# v0_3_0.net
KiCad netlist of a schematic drawn in EAGLE
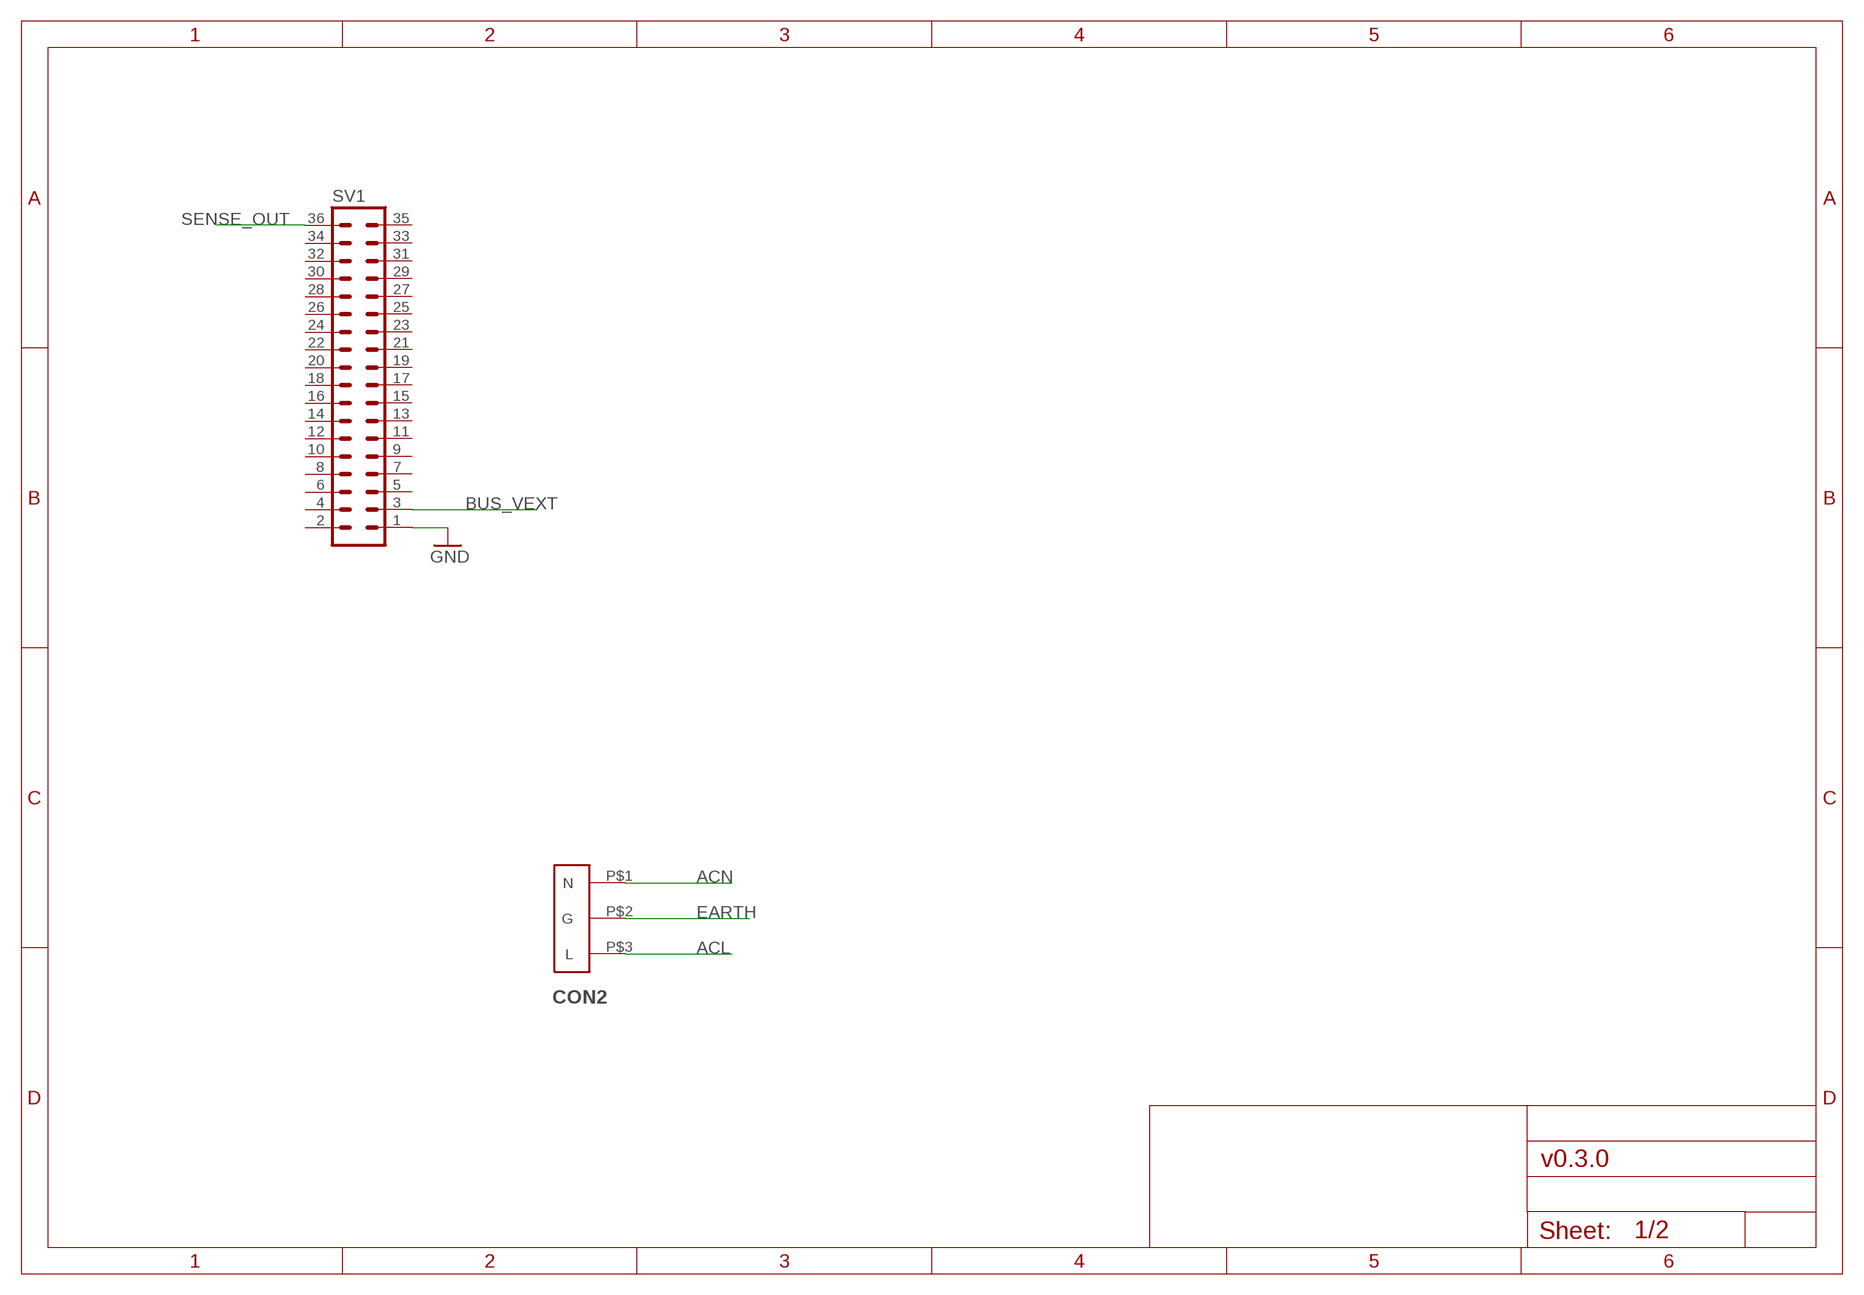
[diagram p0: schematic, sheet 1]
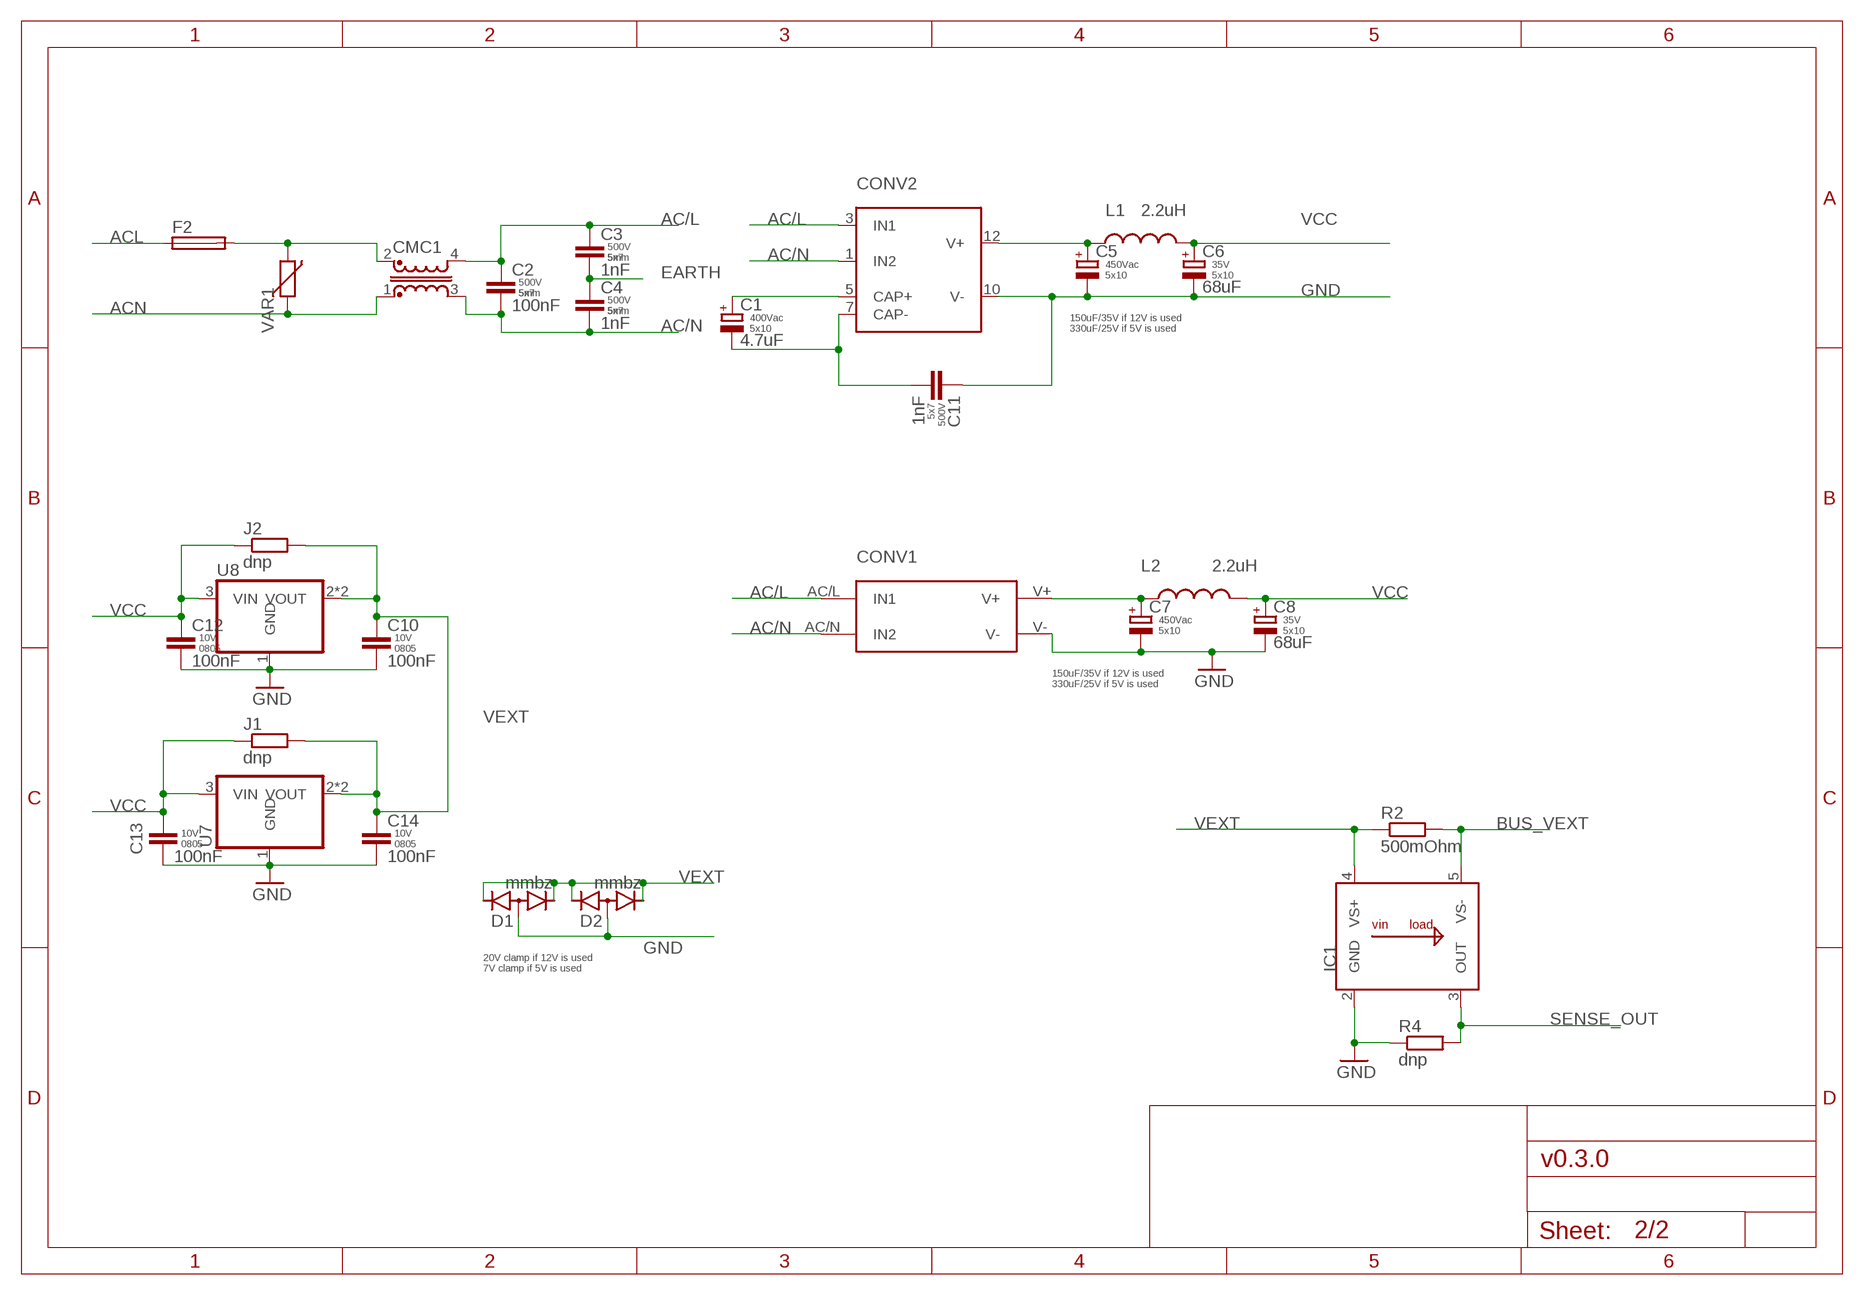
[diagram p1: schematic, sheet 2]

(export (version "E")
  (design (tool "Eeschema 10.0.6"))
  (components
    (comp (ref "CON2")
      (value "4300.0101")
      (footprint "eagle-import:IEC-C6")
      (libsource (lib "eagle-import") (part "4300.0101"))
    )
    (comp (ref "SV1")
      (value "MA18-2")
      (footprint "eagle-import:MA18-2")
      (libsource (lib "eagle-import") (part "MA18-2"))
    )
    (comp (ref "C1")
      (value "4.7uF")
      (footprint "eagle-import:CAPPRD508W65D1000H1600B")
      (fields
        (field (name "PACKAGE") "5x10")
        (field (name "RATING") "450Vac")
        (field (name "RATING_1") "400Vac")
      )
      (libsource (lib "eagle-import") (part "CAP-POL-5PX10WX16H"))
    )
    (comp (ref "C2")
      (value "100nF")
      (footprint "eagle-import:C050-025X075")
      (fields
        (field (name "RATING") "500V")
        (field (name "DIMENSIONS") "5mm")
        (field (name "RATING_1") "500V")
      )
      (libsource (lib "eagle-import") (part "CAP-P5W6H8T2.5"))
    )
    (comp (ref "C3")
      (value "1nF")
      (footprint "eagle-import:C050-025X075")
      (fields
        (field (name "RATING") "500V")
        (field (name "DIMENSIONS") "5mm")
        (field (name "RATING_1") "500V")
      )
      (libsource (lib "eagle-import") (part "CAP-P5W6H8T2.5"))
    )
    (comp (ref "C4")
      (value "1nF")
      (footprint "eagle-import:C050-025X075")
      (fields
        (field (name "RATING") "500V")
        (field (name "DIMENSIONS") "5mm")
        (field (name "RATING_1") "500V")
      )
      (libsource (lib "eagle-import") (part "CAP-P5W6H8T2.5"))
    )
    (comp (ref "C5")
      (value "CAP-POL-5PX10WX16H")
      (footprint "eagle-import:CAPPRD508W65D1000H1600B")
      (libsource (lib "eagle-import") (part "CAP-POL-5PX10WX16H"))
    )
    (comp (ref "C6")
      (value "68uF")
      (footprint "eagle-import:CAPPRD508W65D1000H1600B")
      (fields
        (field (name "PACKAGE") "5x10")
        (field (name "RATING") "450Vac")
        (field (name "RATING_1") "35V")
      )
      (libsource (lib "eagle-import") (part "CAP-POL-5PX10WX16H"))
    )
    (comp (ref "C7")
      (value "CAP-POL-5PX10WX16H")
      (footprint "eagle-import:CAPPRD508W65D1000H1600B")
      (libsource (lib "eagle-import") (part "CAP-POL-5PX10WX16H"))
    )
    (comp (ref "C8")
      (value "68uF")
      (footprint "eagle-import:CAPPRD508W65D1000H1600B")
      (fields
        (field (name "PACKAGE") "5x10")
        (field (name "RATING") "450Vac")
        (field (name "RATING_1") "35V")
      )
      (libsource (lib "eagle-import") (part "CAP-POL-5PX10WX16H"))
    )
    (comp (ref "C10")
      (value "100nF")
      (footprint "eagle-import:C0805")
      (fields (field (name "RATING") "10V") (field (name "PACKAGE") "0805"))
      (libsource (lib "eagle-import") (part "CAP-0805"))
    )
    (comp (ref "C11")
      (value "1nF")
      (footprint "eagle-import:C050-025X075")
      (fields (field (name "RATING") "500V") (field (name "PACKAGE") "5x7"))
      (libsource (lib "eagle-import") (part "CAP-P5W6H8T2.5"))
    )
    (comp (ref "C12")
      (value "100nF")
      (footprint "eagle-import:C0805")
      (libsource (lib "eagle-import") (part "CAP-0805"))
    )
    (comp (ref "C13")
      (value "100nF")
      (footprint "eagle-import:C0805")
      (libsource (lib "eagle-import") (part "CAP-0805"))
    )
    (comp (ref "C14")
      (value "100nF")
      (footprint "eagle-import:C0805")
      (fields (field (name "RATING") "10V") (field (name "PACKAGE") "0805"))
      (libsource (lib "eagle-import") (part "CAP-0805"))
    )
    (comp (ref "CMC1")
      (value "DLD-302U-1A")
      (footprint "eagle-import:DLD")
      (libsource (lib "eagle-import") (part "DLD-302U-1A"))
    )
    (comp (ref "CONV1")
      (value "IRM-03-12V")
      (footprint "eagle-import:IRM-03")
      (libsource (lib "eagle-import") (part "IRM-03-12V"))
    )
    (comp (ref "CONV2")
      (value "AMEOF312SJZ")
      (footprint "eagle-import:AMEOF3-JZ")
      (libsource (lib "eagle-import") (part "AMEOF312SJZ"))
    )
    (comp (ref "D1")
      (value "mmbz")
      (footprint "eagle-import:SOT23")
      (libsource (lib "eagle-import") (part "DIODE-2CA|ACSOT23"))
    )
    (comp (ref "D2")
      (value "mmbz")
      (footprint "eagle-import:SOT23")
      (libsource (lib "eagle-import") (part "DIODE-2CA|ACSOT23"))
    )
    (comp (ref "F2")
      (value "ZH8")
      (footprint "eagle-import:ZH8X2")
      (libsource (lib "eagle-import") (part "ZH8"))
    )
    (comp (ref "IC1")
      (value "ZXCT1021")
      (footprint "eagle-import:SOT95P240X110-5")
      (libsource (lib "eagle-import") (part "ZXCT1021"))
    )
    (comp (ref "J1")
      (value "dnp")
      (footprint "eagle-import:R0805")
      (libsource (lib "eagle-import") (part "R-EU_R0805"))
    )
    (comp (ref "J2")
      (value "dnp")
      (footprint "eagle-import:R0805")
      (libsource (lib "eagle-import") (part "R-EU_R0805"))
    )
    (comp (ref "L1")
      (value "2.2uH")
      (footprint "eagle-import:COIL0608")
      (libsource (lib "eagle-import") (part "COIL0608-0.022"))
    )
    (comp (ref "L2")
      (value "2.2uH")
      (footprint "eagle-import:COIL0608")
      (libsource (lib "eagle-import") (part "COIL0608-0.022"))
    )
    (comp (ref "R2")
      (value "500mOhm")
      (footprint "eagle-import:R0805")
      (libsource (lib "eagle-import") (part "R-EU_R0805"))
    )
    (comp (ref "R4")
      (value "dnp")
      (footprint "eagle-import:R0603")
      (libsource (lib "eagle-import") (part "R-EU_R0603"))
    )
    (comp (ref "U7")
      (value "LD1117S50")
      (footprint "eagle-import:SOT230P700X180-4")
      (libsource (lib "eagle-import") (part "LD1117S50"))
    )
    (comp (ref "U8")
      (value "LD1117S50")
      (footprint "eagle-import:SOT230P700X180-4")
      (libsource (lib "eagle-import") (part "LD1117S50"))
    )
    (comp (ref "VAR1")
      (value "S14K250")
      (footprint "eagle-import:C7.5B4")
      (libsource (lib "eagle-import") (part "S14K250"))
    )
  )
  (nets
    (net (code "1") (name "ACL") (class "Default")
      (node (ref "CON2") (pin "P$3") (pinfunction "L_P$3") (pintype "bidirectional"))
      (node (ref "F2") (pin "1") (pinfunction "1_1") (pintype "passive"))
      (node (ref "F2") (pin "1A") (pinfunction "1_1A") (pintype "passive"))
    )
    (net (code "2") (name "ACN") (class "Default")
      (node (ref "CMC1") (pin "1") (pinfunction "1_1") (pintype "passive"))
      (node (ref "CON2") (pin "P$1") (pinfunction "N_P$1") (pintype "bidirectional"))
      (node (ref "VAR1") (pin "1") (pinfunction "1_1") (pintype "passive"))
    )
    (net (code "3") (name "AC{slash}L") (class "Default")
      (node (ref "C2") (pin "1") (pinfunction "1_1") (pintype "passive"))
      (node (ref "C3") (pin "1") (pinfunction "1_1") (pintype "passive"))
      (node (ref "CMC1") (pin "4") (pinfunction "4_4") (pintype "passive"))
      (node (ref "CONV1") (pin "AC/L") (pinfunction "IN1_AC/L") (pintype "bidirectional"))
      (node (ref "CONV2") (pin "3") (pinfunction "IN1_3") (pintype "bidirectional"))
    )
    (net (code "4") (name "AC{slash}N") (class "Default")
      (node (ref "C2") (pin "2") (pinfunction "2_2") (pintype "passive"))
      (node (ref "C4") (pin "2") (pinfunction "2_2") (pintype "passive"))
      (node (ref "CMC1") (pin "3") (pinfunction "3_3") (pintype "passive"))
      (node (ref "CONV1") (pin "AC/N") (pinfunction "IN2_AC/N") (pintype "bidirectional"))
      (node (ref "CONV2") (pin "1") (pinfunction "IN2_1") (pintype "bidirectional"))
    )
    (net (code "5") (name "BUS_VEXT") (class "Default")
      (node (ref "IC1") (pin "5") (pinfunction "VS-_5") (pintype "bidirectional"))
      (node (ref "R2") (pin "2") (pinfunction "2_2") (pintype "passive"))
      (node (ref "SV1") (pin "3") (pinfunction "3_3") (pintype "passive"))
    )
    (net (code "6") (name "EARTH") (class "Default")
      (node (ref "C3") (pin "2") (pinfunction "2_2") (pintype "passive"))
      (node (ref "C4") (pin "1") (pinfunction "1_1") (pintype "passive"))
      (node (ref "CON2") (pin "P$2") (pinfunction "G_P$2") (pintype "bidirectional"))
    )
    (net (code "7") (name "GND") (class "Default")
      (node (ref "C10") (pin "2") (pinfunction "2_2") (pintype "passive"))
      (node (ref "C11") (pin "1") (pinfunction "1_1") (pintype "passive"))
      (node (ref "C12") (pin "2") (pinfunction "2_2") (pintype "passive"))
      (node (ref "C13") (pin "2") (pinfunction "2_2") (pintype "passive"))
      (node (ref "C14") (pin "2") (pinfunction "2_2") (pintype "passive"))
      (node (ref "C5") (pin "2") (pinfunction "-_2") (pintype "passive"))
      (node (ref "C6") (pin "2") (pinfunction "-_2") (pintype "passive"))
      (node (ref "C7") (pin "2") (pinfunction "-_2") (pintype "passive"))
      (node (ref "C8") (pin "2") (pinfunction "-_2") (pintype "passive"))
      (node (ref "CONV1") (pin "V-") (pinfunction "V-_V-") (pintype "bidirectional"))
      (node (ref "CONV2") (pin "10") (pinfunction "V-_10") (pintype "bidirectional"))
      (node (ref "D1") (pin "3") (pinfunction "A_3") (pintype "passive"))
      (node (ref "D2") (pin "3") (pinfunction "A_3") (pintype "passive"))
      (node (ref "IC1") (pin "2") (pinfunction "GND_2") (pintype "bidirectional"))
      (node (ref "R4") (pin "1") (pinfunction "1_1") (pintype "passive"))
      (node (ref "SV1") (pin "1") (pinfunction "1_1") (pintype "passive"))
      (node (ref "U7") (pin "1") (pinfunction "GND_1") (pintype "power_in"))
      (node (ref "U8") (pin "1") (pinfunction "GND_1") (pintype "power_in"))
    )
    (net (code "8") (name "Net-(C1-+)") (class "Default")
      (node (ref "C1") (pin "1") (pinfunction "+_1") (pintype "passive"))
      (node (ref "CONV2") (pin "5") (pinfunction "CAP+_5") (pintype "bidirectional"))
    )
    (net (code "9") (name "Net-(C1--)") (class "Default")
      (node (ref "C1") (pin "2") (pinfunction "-_2") (pintype "passive"))
      (node (ref "C11") (pin "2") (pinfunction "2_2") (pintype "passive"))
      (node (ref "CONV2") (pin "7") (pinfunction "CAP-_7") (pintype "bidirectional"))
    )
    (net (code "10") (name "Net-(C5-+)") (class "Default")
      (node (ref "C5") (pin "1") (pinfunction "+_1") (pintype "passive"))
      (node (ref "CONV2") (pin "12") (pinfunction "V+_12") (pintype "bidirectional"))
      (node (ref "L1") (pin "P$1") (pinfunction "1_P$1") (pintype "passive"))
    )
    (net (code "11") (name "Net-(C7-+)") (class "Default")
      (node (ref "C7") (pin "1") (pinfunction "+_1") (pintype "passive"))
      (node (ref "CONV1") (pin "V+") (pinfunction "V+_V+") (pintype "bidirectional"))
      (node (ref "L2") (pin "P$1") (pinfunction "1_P$1") (pintype "passive"))
    )
    (net (code "12") (name "Net-(CMC1-Pad2)") (class "Default")
      (node (ref "CMC1") (pin "2") (pinfunction "2_2") (pintype "passive"))
      (node (ref "F2") (pin "2") (pinfunction "2_2") (pintype "passive"))
      (node (ref "F2") (pin "2A") (pinfunction "2_2A") (pintype "passive"))
      (node (ref "VAR1") (pin "2") (pinfunction "2_2") (pintype "passive"))
    )
    (net (code "13") (name "SENSE_OUT") (class "Default")
      (node (ref "IC1") (pin "3") (pinfunction "OUT_3") (pintype "bidirectional"))
      (node (ref "R4") (pin "2") (pinfunction "2_2") (pintype "passive"))
      (node (ref "SV1") (pin "36") (pinfunction "36_36") (pintype "passive"))
    )
    (net (code "14") (name "VCC") (class "Default")
      (node (ref "C12") (pin "1") (pinfunction "1_1") (pintype "passive"))
      (node (ref "C13") (pin "1") (pinfunction "1_1") (pintype "passive"))
      (node (ref "C6") (pin "1") (pinfunction "+_1") (pintype "passive"))
      (node (ref "C8") (pin "1") (pinfunction "+_1") (pintype "passive"))
      (node (ref "J1") (pin "1") (pinfunction "1_1") (pintype "passive"))
      (node (ref "J2") (pin "1") (pinfunction "1_1") (pintype "passive"))
      (node (ref "L1") (pin "P$2") (pinfunction "2_P$2") (pintype "passive"))
      (node (ref "L2") (pin "P$2") (pinfunction "2_P$2") (pintype "passive"))
      (node (ref "U7") (pin "3") (pinfunction "VIN_3") (pintype "input"))
      (node (ref "U8") (pin "3") (pinfunction "VIN_3") (pintype "input"))
    )
    (net (code "15") (name "VEXT") (class "Default")
      (node (ref "C10") (pin "1") (pinfunction "1_1") (pintype "passive"))
      (node (ref "C14") (pin "1") (pinfunction "1_1") (pintype "passive"))
      (node (ref "D1") (pin "1") (pinfunction "K1_1") (pintype "passive"))
      (node (ref "D1") (pin "2") (pinfunction "K2_2") (pintype "passive"))
      (node (ref "D2") (pin "1") (pinfunction "K1_1") (pintype "passive"))
      (node (ref "D2") (pin "2") (pinfunction "K2_2") (pintype "passive"))
      (node (ref "IC1") (pin "4") (pinfunction "VS+_4") (pintype "bidirectional"))
      (node (ref "J1") (pin "2") (pinfunction "2_2") (pintype "passive"))
      (node (ref "J2") (pin "2") (pinfunction "2_2") (pintype "passive"))
      (node (ref "R2") (pin "1") (pinfunction "1_1") (pintype "passive"))
      (node (ref "U7") (pin "2") (pinfunction "VOUT_2") (pintype "output"))
      (node (ref "U7") (pin "4") (pinfunction "VOUT_4") (pintype "output"))
      (node (ref "U8") (pin "2") (pinfunction "VOUT_2") (pintype "output"))
      (node (ref "U8") (pin "4") (pinfunction "VOUT_4") (pintype "output"))
    )
    (net (code "16") (name "unconnected-(SV1-Pad2)") (class "Default")
      (node (ref "SV1") (pin "2") (pinfunction "2_2") (pintype "passive"))
    )
    (net (code "17") (name "unconnected-(SV1-Pad4)") (class "Default")
      (node (ref "SV1") (pin "4") (pinfunction "4_4") (pintype "passive"))
    )
    (net (code "18") (name "unconnected-(SV1-Pad5)") (class "Default")
      (node (ref "SV1") (pin "5") (pinfunction "5_5") (pintype "passive"))
    )
    (net (code "19") (name "unconnected-(SV1-Pad6)") (class "Default")
      (node (ref "SV1") (pin "6") (pinfunction "6_6") (pintype "passive"))
    )
    (net (code "20") (name "unconnected-(SV1-Pad7)") (class "Default")
      (node (ref "SV1") (pin "7") (pinfunction "7_7") (pintype "passive"))
    )
    (net (code "21") (name "unconnected-(SV1-Pad8)") (class "Default")
      (node (ref "SV1") (pin "8") (pinfunction "8_8") (pintype "passive"))
    )
    (net (code "22") (name "unconnected-(SV1-Pad9)") (class "Default")
      (node (ref "SV1") (pin "9") (pinfunction "9_9") (pintype "passive"))
    )
    (net (code "23") (name "unconnected-(SV1-Pad10)") (class "Default")
      (node (ref "SV1") (pin "10") (pinfunction "10_10") (pintype "passive"))
    )
    (net (code "24") (name "unconnected-(SV1-Pad11)") (class "Default")
      (node (ref "SV1") (pin "11") (pinfunction "11_11") (pintype "passive"))
    )
    (net (code "25") (name "unconnected-(SV1-Pad12)") (class "Default")
      (node (ref "SV1") (pin "12") (pinfunction "12_12") (pintype "passive"))
    )
    (net (code "26") (name "unconnected-(SV1-Pad13)") (class "Default")
      (node (ref "SV1") (pin "13") (pinfunction "13_13") (pintype "passive"))
    )
    (net (code "27") (name "unconnected-(SV1-Pad14)") (class "Default")
      (node (ref "SV1") (pin "14") (pinfunction "14_14") (pintype "passive"))
    )
    (net (code "28") (name "unconnected-(SV1-Pad15)") (class "Default")
      (node (ref "SV1") (pin "15") (pinfunction "15_15") (pintype "passive"))
    )
    (net (code "29") (name "unconnected-(SV1-Pad16)") (class "Default")
      (node (ref "SV1") (pin "16") (pinfunction "16_16") (pintype "passive"))
    )
    (net (code "30") (name "unconnected-(SV1-Pad17)") (class "Default")
      (node (ref "SV1") (pin "17") (pinfunction "17_17") (pintype "passive"))
    )
    (net (code "31") (name "unconnected-(SV1-Pad18)") (class "Default")
      (node (ref "SV1") (pin "18") (pinfunction "18_18") (pintype "passive"))
    )
    (net (code "32") (name "unconnected-(SV1-Pad19)") (class "Default")
      (node (ref "SV1") (pin "19") (pinfunction "19_19") (pintype "passive"))
    )
    (net (code "33") (name "unconnected-(SV1-Pad20)") (class "Default")
      (node (ref "SV1") (pin "20") (pinfunction "20_20") (pintype "passive"))
    )
    (net (code "34") (name "unconnected-(SV1-Pad21)") (class "Default")
      (node (ref "SV1") (pin "21") (pinfunction "21_21") (pintype "passive"))
    )
    (net (code "35") (name "unconnected-(SV1-Pad22)") (class "Default")
      (node (ref "SV1") (pin "22") (pinfunction "22_22") (pintype "passive"))
    )
    (net (code "36") (name "unconnected-(SV1-Pad23)") (class "Default")
      (node (ref "SV1") (pin "23") (pinfunction "23_23") (pintype "passive"))
    )
    (net (code "37") (name "unconnected-(SV1-Pad24)") (class "Default")
      (node (ref "SV1") (pin "24") (pinfunction "24_24") (pintype "passive"))
    )
    (net (code "38") (name "unconnected-(SV1-Pad25)") (class "Default")
      (node (ref "SV1") (pin "25") (pinfunction "25_25") (pintype "passive"))
    )
    (net (code "39") (name "unconnected-(SV1-Pad26)") (class "Default")
      (node (ref "SV1") (pin "26") (pinfunction "26_26") (pintype "passive"))
    )
    (net (code "40") (name "unconnected-(SV1-Pad27)") (class "Default")
      (node (ref "SV1") (pin "27") (pinfunction "27_27") (pintype "passive"))
    )
    (net (code "41") (name "unconnected-(SV1-Pad28)") (class "Default")
      (node (ref "SV1") (pin "28") (pinfunction "28_28") (pintype "passive"))
    )
    (net (code "42") (name "unconnected-(SV1-Pad29)") (class "Default")
      (node (ref "SV1") (pin "29") (pinfunction "29_29") (pintype "passive"))
    )
    (net (code "43") (name "unconnected-(SV1-Pad30)") (class "Default")
      (node (ref "SV1") (pin "30") (pinfunction "30_30") (pintype "passive"))
    )
    (net (code "44") (name "unconnected-(SV1-Pad31)") (class "Default")
      (node (ref "SV1") (pin "31") (pinfunction "31_31") (pintype "passive"))
    )
    (net (code "45") (name "unconnected-(SV1-Pad32)") (class "Default")
      (node (ref "SV1") (pin "32") (pinfunction "32_32") (pintype "passive"))
    )
    (net (code "46") (name "unconnected-(SV1-Pad33)") (class "Default")
      (node (ref "SV1") (pin "33") (pinfunction "33_33") (pintype "passive"))
    )
    (net (code "47") (name "unconnected-(SV1-Pad34)") (class "Default")
      (node (ref "SV1") (pin "34") (pinfunction "34_34") (pintype "passive"))
    )
    (net (code "48") (name "unconnected-(SV1-Pad35)") (class "Default")
      (node (ref "SV1") (pin "35") (pinfunction "35_35") (pintype "passive"))
    )
  )
)
